# 7-POWER-USB2TTL.net
KiCad netlist of a schematic drawn in Altium Designer
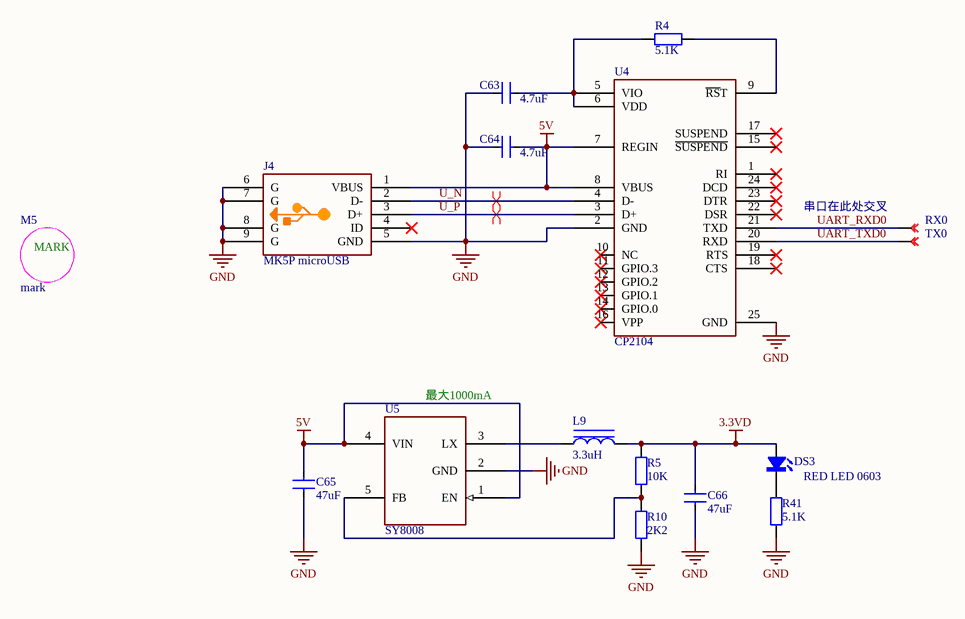
[diagram p0: 7-POWER-USB2TTL.SchDoc]

(export (version "E")
  (design (tool "Eeschema 10.0.6"))
  (components
    (comp (ref "C63")
      (value "4.7uF")
      (footprint "C0402")
      (description "普通小电容")
      (libsource (lib "LIB_MANGO") (part "CAP"))
    )
    (comp (ref "C64")
      (value "4.7uF")
      (footprint "C0402")
      (description "普通小电容")
      (libsource (lib "LIB_MANGO") (part "CAP"))
    )
    (comp (ref "C65")
      (value "47uF")
      (footprint "0805C")
      (description "普通小电容")
      (libsource (lib "LIB_MANGO") (part "CAP"))
    )
    (comp (ref "C66")
      (value "47uF")
      (footprint "0805C")
      (description "普通小电容")
      (libsource (lib "LIB_MANGO") (part "CAP"))
    )
    (comp (ref "DS3")
      (value "RED LED 0603")
      (footprint "LED0603")
      (description "红色0603发光二极管")
      (libsource (lib "LIB_MANGO") (part "LED"))
    )
    (comp (ref "J4")
      (value "MK5P microUSB")
      (footprint "MICROUSB")
      (description "4固定脚microUSB座")
      (libsource (lib "A") (part "MICRO_USB"))
    )
    (comp (ref "L9")
      (value "3.3uH")
      (footprint "VLS3012E")
      (description "vls3012小电感")
      (libsource (lib "LIB_MANGO") (part "L"))
    )
    (comp (ref "M5") (value "mark") (footprint "ZY_UR-3X2") (libsource (lib "LIB_MANGO") (part "mark")))
    (comp (ref "R4")
      (value "5.1K")
      (footprint "R0402")
      (description "普通电阻")
      (libsource (lib "") (part "RES_1"))
    )
    (comp (ref "R5")
      (value "10K")
      (footprint "R0402")
      (description "普通电阻")
      (libsource (lib "LIB_MANGO") (part "RES"))
    )
    (comp (ref "R10")
      (value "2K2")
      (footprint "R0402")
      (description "普通电阻")
      (libsource (lib "LIB_MANGO") (part "RES"))
    )
    (comp (ref "R41")
      (value "5.1K")
      (footprint "R0402")
      (description "普通电阻")
      (libsource (lib "") (part "RES_2"))
    )
    (comp (ref "RX0")
      (value "TEST POINT")
      (footprint "TEST-POINT")
      (description "Description")
      (libsource (lib "LIB_MANGO") (part "TP"))
    )
    (comp (ref "TX0")
      (value "TEST POINT")
      (footprint "TEST-POINT")
      (description "Description")
      (libsource (lib "LIB_MANGO") (part "TP"))
    )
    (comp (ref "U4") (value "CP2104") (footprint "QFN24") (libsource (lib "LIB_MANGO") (part "CP2104")))
    (comp (ref "U5") (value "SY8008") (footprint "SOT23-5") (libsource (lib "LIB_MANGO") (part "SY8008")))
  )
  (nets
    (net (code "1") (name "/UART_RXD0") (class "Default")
      (node (ref "RX0") (pin "1") (pinfunction "1_1") (pintype "passive"))
      (node (ref "U4") (pin "21") (pinfunction "TXD_21") (pintype "passive"))
    )
    (net (code "2") (name "/UART_TXD0") (class "Default")
      (node (ref "TX0") (pin "1") (pinfunction "1_1") (pintype "passive"))
      (node (ref "U4") (pin "20") (pinfunction "RXD_20") (pintype "passive"))
    )
    (net (code "3") (name "/U_N") (class "Default")
      (node (ref "J4") (pin "2") (pinfunction "D-_2") (pintype "passive"))
      (node (ref "U4") (pin "4") (pinfunction "D-_4") (pintype "passive"))
    )
    (net (code "4") (name "/U_P") (class "Default")
      (node (ref "J4") (pin "3") (pinfunction "D+_3") (pintype "passive"))
      (node (ref "U4") (pin "3") (pinfunction "D+_3") (pintype "passive"))
    )
    (net (code "5") (name "3.3VD") (class "Default")
      (node (ref "C66") (pin "2") (pinfunction "2_2") (pintype "passive"))
      (node (ref "DS3") (pin "A") (pinfunction "1_A") (pintype "passive"))
      (node (ref "L9") (pin "1") (pinfunction "1_1") (pintype "passive"))
      (node (ref "R5") (pin "2") (pinfunction "2_2") (pintype "passive"))
    )
    (net (code "6") (name "5V") (class "Default")
      (node (ref "C64") (pin "2") (pinfunction "2_2") (pintype "passive"))
      (node (ref "C65") (pin "1") (pinfunction "1_1") (pintype "passive"))
      (node (ref "J4") (pin "1") (pinfunction "VBUS_1") (pintype "power_in"))
      (node (ref "U4") (pin "7") (pinfunction "REGIN_7") (pintype "passive"))
      (node (ref "U4") (pin "8") (pinfunction "VBUS_8") (pintype "power_in"))
      (node (ref "U5") (pin "1") (pinfunction "EN_1") (pintype "input"))
      (node (ref "U5") (pin "4") (pinfunction "VIN_4") (pintype "power_in"))
    )
    (net (code "7") (name "GND") (class "Default")
      (node (ref "C63") (pin "2") (pinfunction "2_2") (pintype "passive"))
      (node (ref "C64") (pin "1") (pinfunction "1_1") (pintype "passive"))
      (node (ref "C65") (pin "2") (pinfunction "2_2") (pintype "passive"))
      (node (ref "C66") (pin "1") (pinfunction "1_1") (pintype "passive"))
      (node (ref "J4") (pin "5") (pinfunction "GND_5") (pintype "power_in"))
      (node (ref "J4") (pin "6") (pinfunction "G_6") (pintype "passive"))
      (node (ref "J4") (pin "7") (pinfunction "G_7") (pintype "passive"))
      (node (ref "J4") (pin "8") (pinfunction "G_8") (pintype "passive"))
      (node (ref "J4") (pin "9") (pinfunction "G_9") (pintype "passive"))
      (node (ref "R10") (pin "1") (pinfunction "1_1") (pintype "passive"))
      (node (ref "R41") (pin "2") (pinfunction "2_2") (pintype "passive"))
      (node (ref "U4") (pin "2") (pinfunction "GND_2") (pintype "power_in"))
      (node (ref "U4") (pin "25") (pinfunction "GND_25") (pintype "power_in"))
      (node (ref "U5") (pin "2") (pinfunction "GND_2") (pintype "power_in"))
    )
    (net (code "8") (name "Net-(DS3-2)") (class "Default")
      (node (ref "DS3") (pin "K") (pinfunction "2_K") (pintype "passive"))
      (node (ref "R41") (pin "1") (pinfunction "1_1") (pintype "passive"))
    )
    (net (code "9") (name "Net-(U4-VDD)") (class "Default")
      (node (ref "C63") (pin "1") (pinfunction "1_1") (pintype "passive"))
      (node (ref "R4") (pin "1") (pinfunction "1_1") (pintype "passive"))
      (node (ref "U4") (pin "5") (pinfunction "VIO_5") (pintype "passive"))
      (node (ref "U4") (pin "6") (pinfunction "VDD_6") (pintype "passive"))
    )
    (net (code "10") (name "Net-(U4-~{RS}T)") (class "Default")
      (node (ref "R4") (pin "2") (pinfunction "2_2") (pintype "passive"))
      (node (ref "U4") (pin "9") (pinfunction "~{RS}T_9") (pintype "passive"))
    )
    (net (code "11") (name "Net-(U5-FB)") (class "Default")
      (node (ref "R10") (pin "2") (pinfunction "2_2") (pintype "passive"))
      (node (ref "R5") (pin "1") (pinfunction "1_1") (pintype "passive"))
      (node (ref "U5") (pin "5") (pinfunction "FB_5") (pintype "passive"))
    )
    (net (code "12") (name "Net-(U5-LX)") (class "Default")
      (node (ref "L9") (pin "2") (pinfunction "2_2") (pintype "passive"))
      (node (ref "U5") (pin "3") (pinfunction "LX_3") (pintype "passive"))
    )
    (net (code "13") (name "unconnected-(J4-ID-Pad4)") (class "Default")
      (node (ref "J4") (pin "4") (pinfunction "ID_4") (pintype "passive+no_connect"))
    )
    (net (code "14") (name "unconnected-(U4-CTS-Pad18)") (class "Default")
      (node (ref "U4") (pin "18") (pinfunction "CTS_18") (pintype "passive+no_connect"))
    )
    (net (code "15") (name "unconnected-(U4-DCD-Pad24)") (class "Default")
      (node (ref "U4") (pin "24") (pinfunction "DCD_24") (pintype "passive+no_connect"))
    )
    (net (code "16") (name "unconnected-(U4-DSR-Pad22)") (class "Default")
      (node (ref "U4") (pin "22") (pinfunction "DSR_22") (pintype "passive+no_connect"))
    )
    (net (code "17") (name "unconnected-(U4-DTR-Pad23)") (class "Default")
      (node (ref "U4") (pin "23") (pinfunction "DTR_23") (pintype "passive+no_connect"))
    )
    (net (code "18") (name "unconnected-(U4-GPIO.0-Pad14)") (class "Default")
      (node (ref "U4") (pin "14") (pinfunction "GPIO.0_14") (pintype "passive+no_connect"))
    )
    (net (code "19") (name "unconnected-(U4-GPIO.1-Pad13)") (class "Default")
      (node (ref "U4") (pin "13") (pinfunction "GPIO.1_13") (pintype "passive+no_connect"))
    )
    (net (code "20") (name "unconnected-(U4-GPIO.2-Pad12)") (class "Default")
      (node (ref "U4") (pin "12") (pinfunction "GPIO.2_12") (pintype "passive+no_connect"))
    )
    (net (code "21") (name "unconnected-(U4-GPIO.3-Pad11)") (class "Default")
      (node (ref "U4") (pin "11") (pinfunction "GPIO.3_11") (pintype "passive+no_connect"))
    )
    (net (code "22") (name "unconnected-(U4-NC-Pad10)") (class "Default")
      (node (ref "U4") (pin "10") (pinfunction "NC_10") (pintype "passive+no_connect"))
    )
    (net (code "23") (name "unconnected-(U4-RI-Pad1)") (class "Default")
      (node (ref "U4") (pin "1") (pinfunction "RI_1") (pintype "passive+no_connect"))
    )
    (net (code "24") (name "unconnected-(U4-RTS-Pad19)") (class "Default")
      (node (ref "U4") (pin "19") (pinfunction "RTS_19") (pintype "passive+no_connect"))
    )
    (net (code "25") (name "unconnected-(U4-SUSPEND-Pad17)") (class "Default")
      (node (ref "U4") (pin "17") (pinfunction "SUSPEND_17") (pintype "passive+no_connect"))
    )
    (net (code "26") (name "unconnected-(U4-VPP-Pad16)") (class "Default")
      (node (ref "U4") (pin "16") (pinfunction "VPP_16") (pintype "passive+no_connect"))
    )
    (net (code "27") (name "unconnected-(U4-~{SUSPEND}-Pad15)") (class "Default")
      (node (ref "U4") (pin "15") (pinfunction "~{SUSPEND}_15") (pintype "passive+no_connect"))
    )
  )
)
